# esp32.net
KiCad netlist of a schematic drawn in Altium Designer
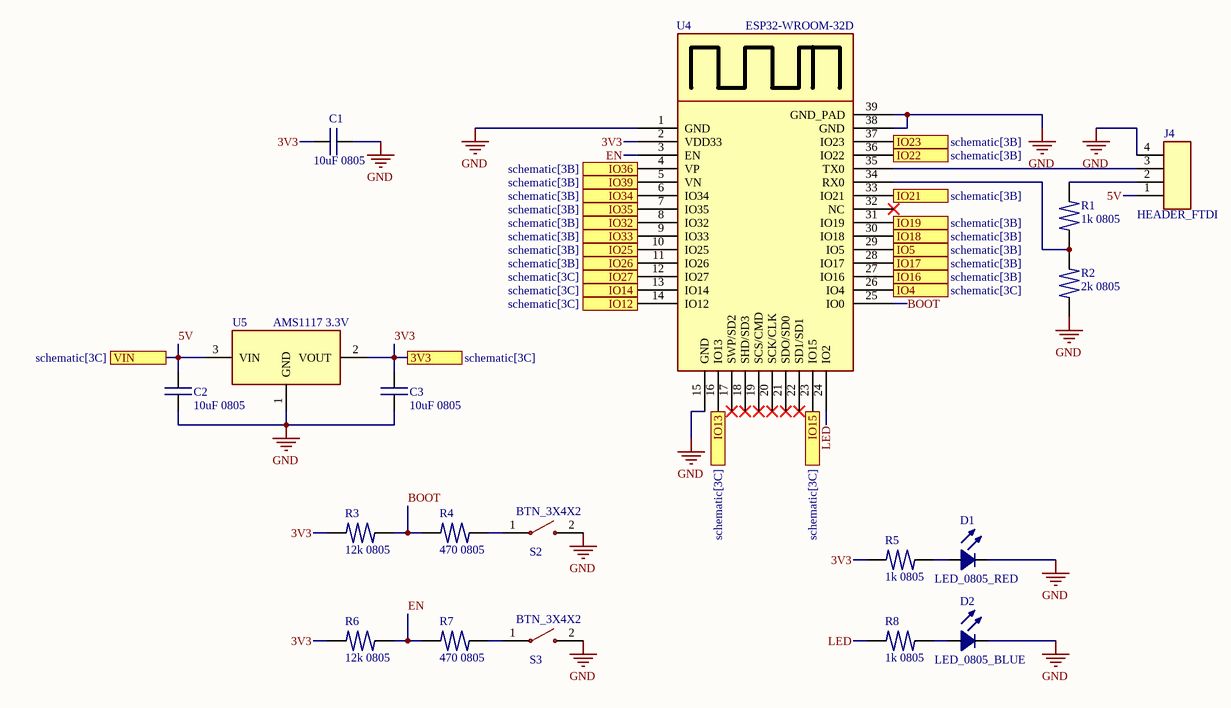
[diagram p0: esp32.SchDoc]

(export (version "E")
  (design (tool "Eeschema 10.0.6"))
  (components
    (comp (ref "C1")
      (value "10uF 0805")
      (footprint "CAPACITOR 0805")
      (description "Generic Capacitor 0805, 2x1.25x1.4mm.")
      (libsource (lib "Ceramic Capacitor") (part "CAPACITOR 0805"))
    )
    (comp (ref "C2")
      (value "10uF 0805")
      (footprint "CAPACITOR 0805")
      (description "Generic Capacitor 0805, 2x1.25x1.4mm.")
      (libsource (lib "Ceramic Capacitor") (part "CAPACITOR 0805"))
    )
    (comp (ref "C3")
      (value "10uF 0805")
      (footprint "CAPACITOR 0805")
      (description "Generic Capacitor 0805, 2x1.25x1.4mm.")
      (libsource (lib "Ceramic Capacitor") (part "CAPACITOR 0805"))
    )
    (comp (ref "D1")
      (value "LED_0805_RED")
      (footprint "LED_0805_RED")
      (libsource (lib "LED") (part "LED_0805_RED"))
    )
    (comp (ref "D2")
      (value "LED_0805_BLUE")
      (footprint "LED_0805_BLUE")
      (libsource (lib "LED") (part "LED_0805_BLUE"))
    )
    (comp (ref "J4")
      (value "HEADER_FTDI")
      (footprint "MALE-2.54-4P")
      (description "Male Header Connector 2.54mm 4 Pins.")
      (libsource (lib "Connectors") (part "MALE-2.54-4P"))
    )
    (comp (ref "R1")
      (value "1k 0805")
      (footprint "RESISTOR_0805")
      (description "Resistor SMD 0805 (1K)")
      (libsource (lib "Resistors") (part "RESISTOR_0805"))
    )
    (comp (ref "R2")
      (value "2k 0805")
      (footprint "RESISTOR_0805")
      (description "Resistor SMD 0805 (1K)")
      (libsource (lib "Resistors") (part "RESISTOR_0805"))
    )
    (comp (ref "R3")
      (value "12k 0805")
      (footprint "RESISTOR_0805")
      (libsource (lib "Resistors") (part "RESISTOR_0805"))
    )
    (comp (ref "R4")
      (value "470 0805")
      (footprint "RESISTOR_0805")
      (libsource (lib "Resistors") (part "RESISTOR_0805"))
    )
    (comp (ref "R5")
      (value "1k 0805")
      (footprint "RESISTOR_0805")
      (description "Resistor SMD 0805 (1K)")
      (libsource (lib "Resistors") (part "RESISTOR_0805"))
    )
    (comp (ref "R6")
      (value "12k 0805")
      (footprint "RESISTOR_0805")
      (libsource (lib "Resistors") (part "RESISTOR_0805"))
    )
    (comp (ref "R7")
      (value "470 0805")
      (footprint "RESISTOR_0805")
      (libsource (lib "Resistors") (part "RESISTOR_0805"))
    )
    (comp (ref "R8")
      (value "1k 0805")
      (footprint "RESISTOR_0805")
      (libsource (lib "Resistors") (part "RESISTOR_0805"))
    )
    (comp (ref "S2")
      (value "BTN_3X4X2")
      (footprint "PUSH_BUTTON_SMD_3X4X2")
      (description "Push Button Tactile Switch SMD 2 Pins 3x4x2mm.")
      (libsource (lib "Buttons & Switches") (part "PUSH_BUTTON_SMD_3X4X2"))
    )
    (comp (ref "S3")
      (value "BTN_3X4X2")
      (footprint "PUSH_BUTTON_SMD_3X4X2")
      (description "Push Button Tactile Switch SMD 2 Pins 3x4x2mm.")
      (libsource (lib "Buttons & Switches") (part "PUSH_BUTTON_SMD_3X4X2"))
    )
    (comp (ref "U4")
      (value "ESP32-WROOM-32D")
      (footprint "ESP32-WROOM-32D")
      (description "Chip SMD 39 Pads Wifi 2.4GHz BLE 4.2 18x25.5mm w/ Antenna.")
      (libsource (lib "Espressif Microcontrollers") (part "ESP32-WROOM-32D"))
    )
    (comp (ref "U5")
      (value "AMS1117 3.3V")
      (footprint "AMS1117")
      (description "IC REG LINEAR 1A SOT-89-3L")
      (libsource (lib "Voltage Regulators") (part "AMS1117"))
    )
  )
  (nets
    (net (code "1") (name "/3V3") (class "Default")
      (node (ref "C1") (pin "1") (pinfunction "1_1") (pintype "passive"))
      (node (ref "C3") (pin "2") (pinfunction "2_2") (pintype "passive"))
      (node (ref "R3") (pin "2") (pinfunction "2_2") (pintype "passive"))
      (node (ref "R5") (pin "2") (pinfunction "2_2") (pintype "passive"))
      (node (ref "R6") (pin "2") (pinfunction "2_2") (pintype "passive"))
      (node (ref "U4") (pin "2") (pinfunction "VDD33_2") (pintype "passive"))
      (node (ref "U5") (pin "2") (pinfunction "VOUT_2") (pintype "passive"))
    )
    (net (code "2") (name "/5V") (class "Default")
      (node (ref "C2") (pin "2") (pinfunction "2_2") (pintype "passive"))
      (node (ref "J4") (pin "1") (pintype "passive"))
      (node (ref "U5") (pin "3") (pinfunction "VIN_3") (pintype "passive"))
    )
    (net (code "3") (name "/BOOT") (class "Default")
      (node (ref "R3") (pin "1") (pinfunction "1_1") (pintype "passive"))
      (node (ref "R4") (pin "2") (pinfunction "2_2") (pintype "passive"))
      (node (ref "U4") (pin "25") (pinfunction "IO0_25") (pintype "passive"))
    )
    (net (code "4") (name "/EN") (class "Default")
      (node (ref "R6") (pin "1") (pinfunction "1_1") (pintype "passive"))
      (node (ref "R7") (pin "2") (pinfunction "2_2") (pintype "passive"))
      (node (ref "U4") (pin "3") (pinfunction "EN_3") (pintype "passive"))
    )
    (net (code "5") (name "/IO4") (class "Default")
      (node (ref "U4") (pin "26") (pinfunction "IO4_26") (pintype "passive"))
    )
    (net (code "6") (name "/IO5") (class "Default")
      (node (ref "U4") (pin "29") (pinfunction "IO5_29") (pintype "passive"))
    )
    (net (code "7") (name "/IO12") (class "Default")
      (node (ref "U4") (pin "14") (pinfunction "IO12_14") (pintype "passive"))
    )
    (net (code "8") (name "/IO13") (class "Default")
      (node (ref "U4") (pin "16") (pinfunction "IO13_16") (pintype "passive"))
    )
    (net (code "9") (name "/IO14") (class "Default")
      (node (ref "U4") (pin "13") (pinfunction "IO14_13") (pintype "passive"))
    )
    (net (code "10") (name "/IO15") (class "Default")
      (node (ref "U4") (pin "23") (pinfunction "IO15_23") (pintype "passive"))
    )
    (net (code "11") (name "/IO16") (class "Default")
      (node (ref "U4") (pin "27") (pinfunction "IO16_27") (pintype "passive"))
    )
    (net (code "12") (name "/IO17") (class "Default")
      (node (ref "U4") (pin "28") (pinfunction "IO17_28") (pintype "passive"))
    )
    (net (code "13") (name "/IO18") (class "Default")
      (node (ref "U4") (pin "30") (pinfunction "IO18_30") (pintype "passive"))
    )
    (net (code "14") (name "/IO19") (class "Default")
      (node (ref "U4") (pin "31") (pinfunction "IO19_31") (pintype "passive"))
    )
    (net (code "15") (name "/IO21") (class "Default")
      (node (ref "U4") (pin "33") (pinfunction "IO21_33") (pintype "passive"))
    )
    (net (code "16") (name "/IO22") (class "Default")
      (node (ref "U4") (pin "36") (pinfunction "IO22_36") (pintype "passive"))
    )
    (net (code "17") (name "/IO23") (class "Default")
      (node (ref "U4") (pin "37") (pinfunction "IO23_37") (pintype "passive"))
    )
    (net (code "18") (name "/IO25") (class "Default")
      (node (ref "U4") (pin "10") (pinfunction "IO25_10") (pintype "passive"))
    )
    (net (code "19") (name "/IO26") (class "Default")
      (node (ref "U4") (pin "11") (pinfunction "IO26_11") (pintype "passive"))
    )
    (net (code "20") (name "/IO27") (class "Default")
      (node (ref "U4") (pin "12") (pinfunction "IO27_12") (pintype "passive"))
    )
    (net (code "21") (name "/IO32") (class "Default")
      (node (ref "U4") (pin "8") (pinfunction "IO32_8") (pintype "passive"))
    )
    (net (code "22") (name "/IO33") (class "Default")
      (node (ref "U4") (pin "9") (pinfunction "IO33_9") (pintype "passive"))
    )
    (net (code "23") (name "/IO34") (class "Default")
      (node (ref "U4") (pin "6") (pinfunction "IO34_6") (pintype "passive"))
    )
    (net (code "24") (name "/IO35") (class "Default")
      (node (ref "U4") (pin "7") (pinfunction "IO35_7") (pintype "passive"))
    )
    (net (code "25") (name "/IO36") (class "Default")
      (node (ref "U4") (pin "4") (pinfunction "VP_4") (pintype "passive"))
    )
    (net (code "26") (name "/IO39") (class "Default")
      (node (ref "U4") (pin "5") (pinfunction "VN_5") (pintype "passive"))
    )
    (net (code "27") (name "/LED") (class "Default")
      (node (ref "R8") (pin "1") (pinfunction "1_1") (pintype "passive"))
      (node (ref "U4") (pin "24") (pinfunction "IO2_24") (pintype "passive"))
    )
    (net (code "28") (name "GND") (class "Default")
      (node (ref "C1") (pin "2") (pinfunction "2_2") (pintype "passive"))
      (node (ref "C2") (pin "1") (pinfunction "1_1") (pintype "passive"))
      (node (ref "C3") (pin "1") (pinfunction "1_1") (pintype "passive"))
      (node (ref "D1") (pin "2") (pinfunction "2_2") (pintype "passive"))
      (node (ref "D2") (pin "2") (pinfunction "2_2") (pintype "passive"))
      (node (ref "J4") (pin "4") (pintype "passive"))
      (node (ref "R2") (pin "1") (pinfunction "1_1") (pintype "passive"))
      (node (ref "S2") (pin "2") (pinfunction "2_2") (pintype "passive"))
      (node (ref "S3") (pin "2") (pinfunction "2_2") (pintype "passive"))
      (node (ref "U4") (pin "1") (pinfunction "GND_1") (pintype "passive"))
      (node (ref "U4") (pin "15") (pinfunction "GND_15") (pintype "passive"))
      (node (ref "U4") (pin "38") (pinfunction "GND_38") (pintype "passive"))
      (node (ref "U4") (pin "39") (pinfunction "GND_PAD_39") (pintype "passive"))
      (node (ref "U5") (pin "1") (pinfunction "GND_1") (pintype "passive"))
    )
    (net (code "29") (name "Net-(D1-Pad1)") (class "Default")
      (node (ref "D1") (pin "1") (pinfunction "1_1") (pintype "passive"))
      (node (ref "R5") (pin "1") (pinfunction "1_1") (pintype "passive"))
    )
    (net (code "30") (name "Net-(D2-Pad1)") (class "Default")
      (node (ref "D2") (pin "1") (pinfunction "1_1") (pintype "passive"))
      (node (ref "R8") (pin "2") (pinfunction "2_2") (pintype "passive"))
    )
    (net (code "31") (name "Net-(J4-Pad2)") (class "Default")
      (node (ref "J4") (pin "2") (pintype "passive"))
      (node (ref "R1") (pin "2") (pinfunction "2_2") (pintype "passive"))
    )
    (net (code "32") (name "Net-(R4-Pad1)") (class "Default")
      (node (ref "R4") (pin "1") (pinfunction "1_1") (pintype "passive"))
      (node (ref "S2") (pin "1") (pinfunction "1_1") (pintype "passive"))
    )
    (net (code "33") (name "Net-(R7-Pad1)") (class "Default")
      (node (ref "R7") (pin "1") (pinfunction "1_1") (pintype "passive"))
      (node (ref "S3") (pin "1") (pinfunction "1_1") (pintype "passive"))
    )
    (net (code "34") (name "Net-(U4-RX0)") (class "Default")
      (node (ref "R1") (pin "1") (pinfunction "1_1") (pintype "passive"))
      (node (ref "R2") (pin "2") (pinfunction "2_2") (pintype "passive"))
      (node (ref "U4") (pin "34") (pinfunction "RX0_34") (pintype "passive"))
    )
    (net (code "35") (name "Net-(U4-TX0)") (class "Default")
      (node (ref "J4") (pin "3") (pintype "passive"))
      (node (ref "U4") (pin "35") (pinfunction "TX0_35") (pintype "passive"))
    )
    (net (code "36") (name "unconnected-(U4-NC-Pad32)") (class "Default")
      (node (ref "U4") (pin "32") (pinfunction "NC_32") (pintype "passive+no_connect"))
    )
    (net (code "37") (name "unconnected-(U4-SCK{slash}CLK-Pad20)") (class "Default")
      (node (ref "U4") (pin "20") (pinfunction "SCK/CLK_20") (pintype "passive+no_connect"))
    )
    (net (code "38") (name "unconnected-(U4-SCS{slash}CMD-Pad19)") (class "Default")
      (node (ref "U4") (pin "19") (pinfunction "SCS/CMD_19") (pintype "passive+no_connect"))
    )
    (net (code "39") (name "unconnected-(U4-SD1{slash}SD1-Pad22)") (class "Default")
      (node (ref "U4") (pin "22") (pinfunction "SD1/SD1_22") (pintype "passive+no_connect"))
    )
    (net (code "40") (name "unconnected-(U4-SDO{slash}SD0-Pad21)") (class "Default")
      (node (ref "U4") (pin "21") (pinfunction "SDO/SD0_21") (pintype "passive+no_connect"))
    )
    (net (code "41") (name "unconnected-(U4-SHD{slash}SD3-Pad18)") (class "Default")
      (node (ref "U4") (pin "18") (pinfunction "SHD/SD3_18") (pintype "passive+no_connect"))
    )
    (net (code "42") (name "unconnected-(U4-SWP{slash}SD2-Pad17)") (class "Default")
      (node (ref "U4") (pin "17") (pinfunction "SWP/SD2_17") (pintype "passive+no_connect"))
    )
  )
)
